# Tetris.net
KiCad netlist of a schematic drawn in EAGLE
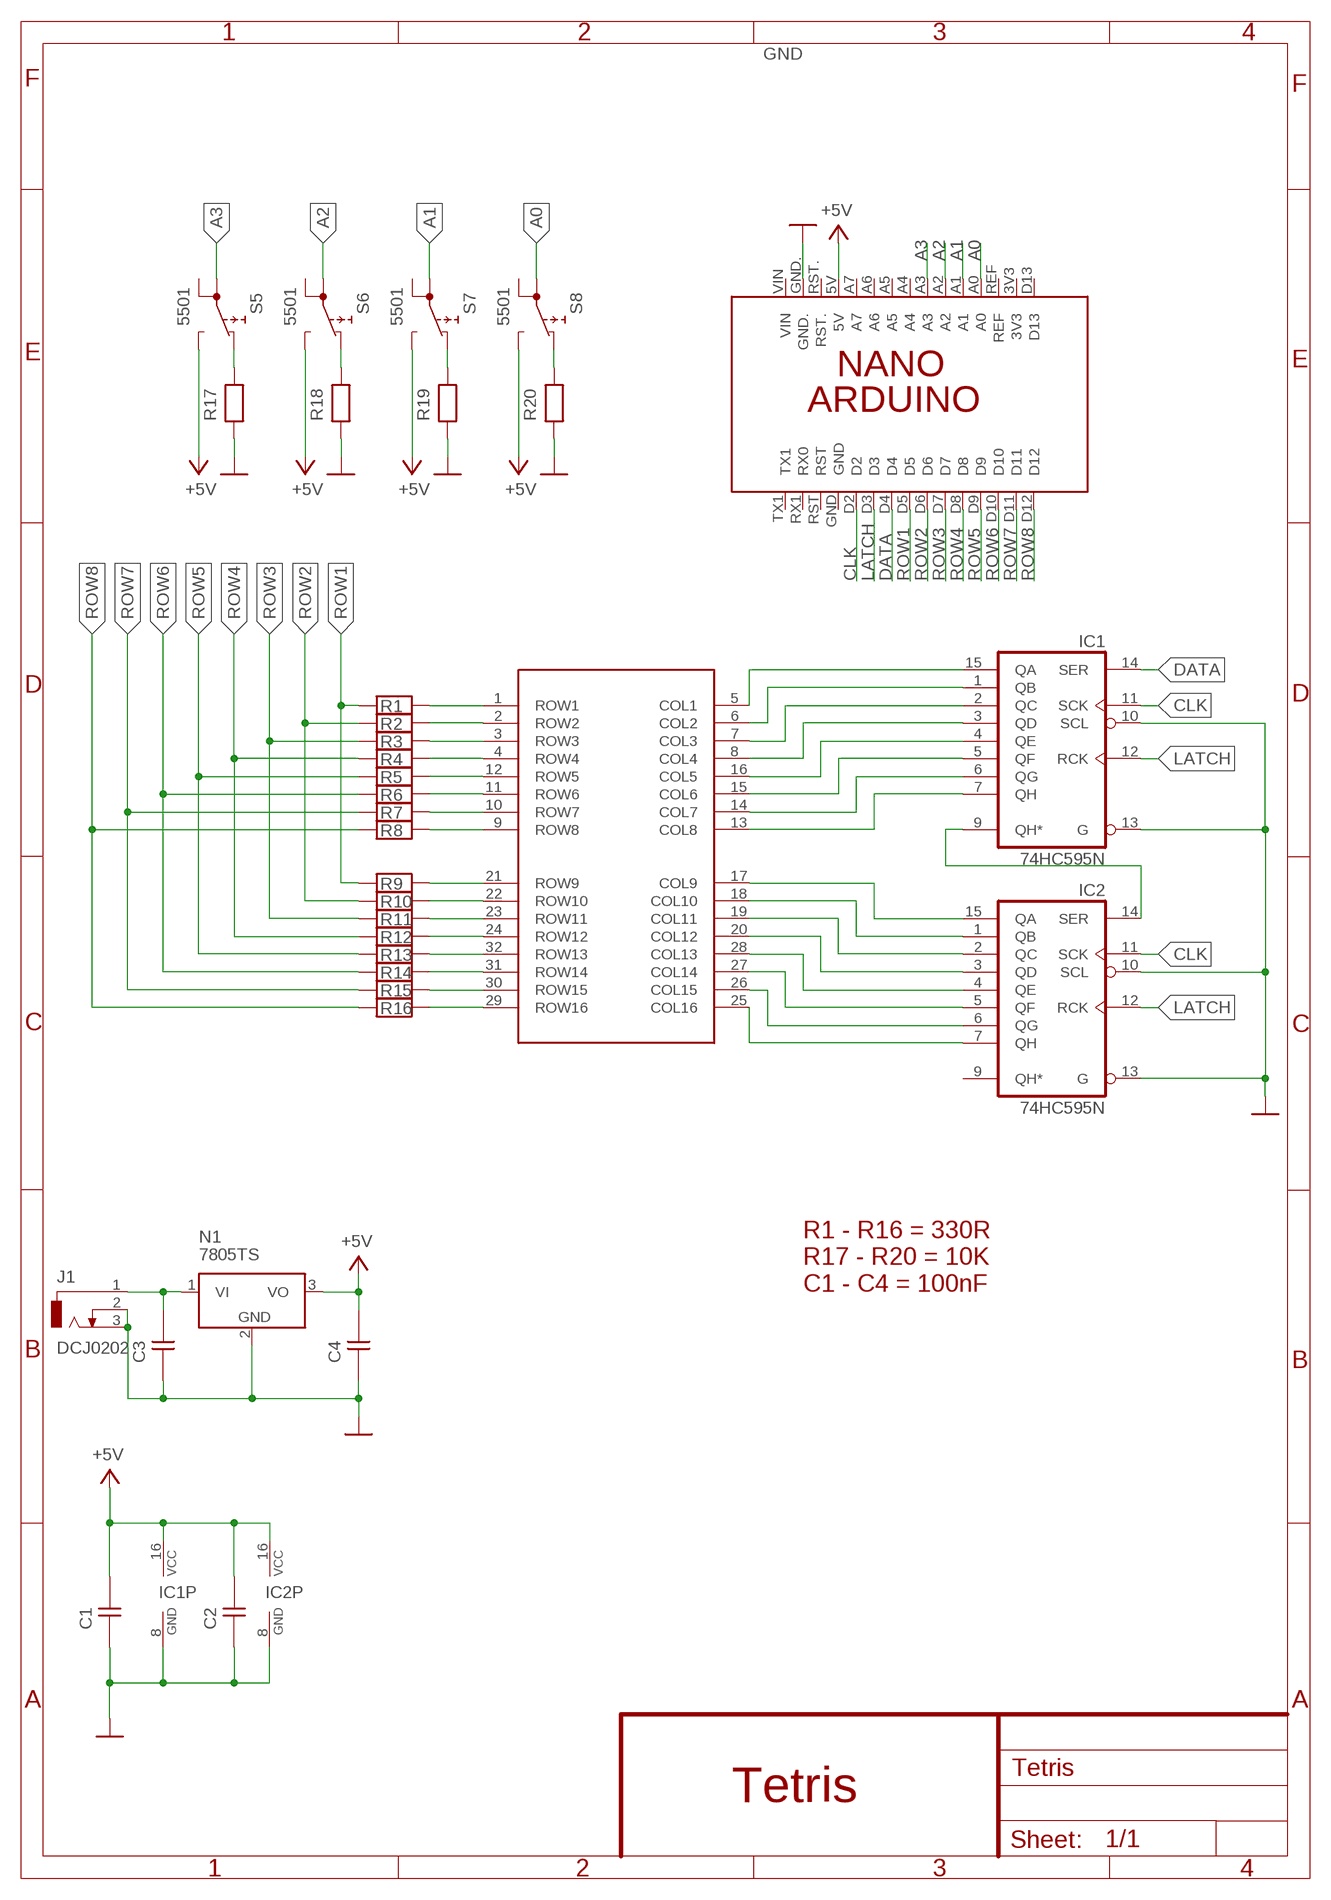
[diagram p0: schematic, sheet 1]

(export (version "E")
  (design (tool "Eeschema 10.0.6"))
  (components
    (comp (ref "C1")
      (value "C-7.5")
      (footprint "eagle-import:C-7,5")
      (libsource (lib "eagle-import") (part "C-7.5"))
    )
    (comp (ref "C2")
      (value "C-7.5")
      (footprint "eagle-import:C-7,5")
      (libsource (lib "eagle-import") (part "C-7.5"))
    )
    (comp (ref "C3")
      (value "C-7.5")
      (footprint "eagle-import:C-7,5")
      (libsource (lib "eagle-import") (part "C-7.5"))
    )
    (comp (ref "C4")
      (value "C-7.5")
      (footprint "eagle-import:C-7,5")
      (libsource (lib "eagle-import") (part "C-7.5"))
    )
    (comp (ref "IC1")
      (value "74HC595N")
      (footprint "eagle-import:DIL16")
      (libsource (lib "eagle-import") (part "74595NHC"))
    )
    (comp (ref "IC2")
      (value "74HC595N")
      (footprint "eagle-import:DIL16")
      (libsource (lib "eagle-import") (part "74595NHC"))
    )
    (comp (ref "J1")
      (value "DCJ0202")
      (footprint "eagle-import:DCJ0202")
      (libsource (lib "eagle-import") (part "DCJ0202"))
    )
    (comp (ref "N1")
      (value "7805TS")
      (footprint "eagle-import:TO-220S")
      (libsource (lib "eagle-import") (part "7805TS"))
    )
    (comp (ref "PCB1")
      (value "ARDUINO_NANO")
      (footprint "eagle-import:ARDUINO_NANO")
      (libsource (lib "eagle-import") (part "ARDUINO_NANO"))
    )
    (comp (ref "R1")
      (value "R-10")
      (footprint "eagle-import:R-10")
      (libsource (lib "eagle-import") (part "R-10"))
    )
    (comp (ref "R2")
      (value "R-10")
      (footprint "eagle-import:R-10")
      (libsource (lib "eagle-import") (part "R-10"))
    )
    (comp (ref "R3")
      (value "R-10")
      (footprint "eagle-import:R-10")
      (libsource (lib "eagle-import") (part "R-10"))
    )
    (comp (ref "R4")
      (value "R-10")
      (footprint "eagle-import:R-10")
      (libsource (lib "eagle-import") (part "R-10"))
    )
    (comp (ref "R5")
      (value "R-10")
      (footprint "eagle-import:R-10")
      (libsource (lib "eagle-import") (part "R-10"))
    )
    (comp (ref "R6")
      (value "R-10")
      (footprint "eagle-import:R-10")
      (libsource (lib "eagle-import") (part "R-10"))
    )
    (comp (ref "R7")
      (value "R-10")
      (footprint "eagle-import:R-10")
      (libsource (lib "eagle-import") (part "R-10"))
    )
    (comp (ref "R8")
      (value "R-10")
      (footprint "eagle-import:R-10")
      (libsource (lib "eagle-import") (part "R-10"))
    )
    (comp (ref "R9")
      (value "R-10")
      (footprint "eagle-import:R-10")
      (libsource (lib "eagle-import") (part "R-10"))
    )
    (comp (ref "R10")
      (value "R-10")
      (footprint "eagle-import:R-10")
      (libsource (lib "eagle-import") (part "R-10"))
    )
    (comp (ref "R11")
      (value "R-10")
      (footprint "eagle-import:R-10")
      (libsource (lib "eagle-import") (part "R-10"))
    )
    (comp (ref "R12")
      (value "R-10")
      (footprint "eagle-import:R-10")
      (libsource (lib "eagle-import") (part "R-10"))
    )
    (comp (ref "R13")
      (value "R-10")
      (footprint "eagle-import:R-10")
      (libsource (lib "eagle-import") (part "R-10"))
    )
    (comp (ref "R14")
      (value "R-10")
      (footprint "eagle-import:R-10")
      (libsource (lib "eagle-import") (part "R-10"))
    )
    (comp (ref "R15")
      (value "R-10")
      (footprint "eagle-import:R-10")
      (libsource (lib "eagle-import") (part "R-10"))
    )
    (comp (ref "R16")
      (value "R-10")
      (footprint "eagle-import:R-10")
      (libsource (lib "eagle-import") (part "R-10"))
    )
    (comp (ref "R17")
      (value "R-10")
      (footprint "eagle-import:R-10")
      (libsource (lib "eagle-import") (part "R-10"))
    )
    (comp (ref "R18")
      (value "R-10")
      (footprint "eagle-import:R-10")
      (libsource (lib "eagle-import") (part "R-10"))
    )
    (comp (ref "R19")
      (value "R-10")
      (footprint "eagle-import:R-10")
      (libsource (lib "eagle-import") (part "R-10"))
    )
    (comp (ref "R20")
      (value "R-10")
      (footprint "eagle-import:R-10")
      (libsource (lib "eagle-import") (part "R-10"))
    )
    (comp (ref "S5")
      (value "5501")
      (footprint "eagle-import:5501")
      (libsource (lib "eagle-import") (part "55?01"))
    )
    (comp (ref "S6")
      (value "5501")
      (footprint "eagle-import:5501")
      (libsource (lib "eagle-import") (part "55?01"))
    )
    (comp (ref "S7")
      (value "5501")
      (footprint "eagle-import:5501")
      (libsource (lib "eagle-import") (part "55?01"))
    )
    (comp (ref "S8")
      (value "5501")
      (footprint "eagle-import:5501")
      (libsource (lib "eagle-import") (part "55?01"))
    )
    (comp (ref "U$9")
      (value "DOT_MATRIX")
      (footprint "eagle-import:SH")
      (libsource (lib "eagle-import") (part "DOT_MATRIX"))
    )
  )
  (nets
    (net (code "1") (name "+5V") (class "Default")
      (node (ref "C1") (pin "2") (pinfunction "2_2") (pintype "passive"))
      (node (ref "C2") (pin "2") (pinfunction "2_2") (pintype "passive"))
      (node (ref "C4") (pin "2") (pinfunction "2_2") (pintype "passive"))
      (node (ref "IC1") (pin "16") (pinfunction "VCC_16") (pintype "power_in"))
      (node (ref "IC2") (pin "16") (pinfunction "VCC_16") (pintype "power_in"))
      (node (ref "N1") (pin "3") (pinfunction "VO_3") (pintype "output"))
      (node (ref "PCB1") (pin "5V") (pinfunction "5V_5V") (pintype "bidirectional"))
      (node (ref "S5") (pin "NC") (pinfunction "NO_NC") (pintype "passive"))
      (node (ref "S6") (pin "NC") (pinfunction "NO_NC") (pintype "passive"))
      (node (ref "S7") (pin "NC") (pinfunction "NO_NC") (pintype "passive"))
      (node (ref "S8") (pin "NC") (pinfunction "NO_NC") (pintype "passive"))
    )
    (net (code "2") (name "A0") (class "Default")
      (node (ref "PCB1") (pin "A0") (pinfunction "A0_A0") (pintype "bidirectional"))
      (node (ref "S8") (pin "1A") (pinfunction "1A_1A") (pintype "passive"))
    )
    (net (code "3") (name "A1") (class "Default")
      (node (ref "PCB1") (pin "A1") (pinfunction "A1_A1") (pintype "bidirectional"))
      (node (ref "S7") (pin "1A") (pinfunction "1A_1A") (pintype "passive"))
    )
    (net (code "4") (name "A2") (class "Default")
      (node (ref "PCB1") (pin "A2") (pinfunction "A2_A2") (pintype "bidirectional"))
      (node (ref "S6") (pin "1A") (pinfunction "1A_1A") (pintype "passive"))
    )
    (net (code "5") (name "A3") (class "Default")
      (node (ref "PCB1") (pin "A3") (pinfunction "A3_A3") (pintype "bidirectional"))
      (node (ref "S5") (pin "1A") (pinfunction "1A_1A") (pintype "passive"))
    )
    (net (code "6") (name "CLK") (class "Default")
      (node (ref "IC1") (pin "11") (pinfunction "SCK_11") (pintype "input"))
      (node (ref "IC2") (pin "11") (pinfunction "SCK_11") (pintype "input"))
      (node (ref "PCB1") (pin "D2") (pinfunction "D2_D2") (pintype "bidirectional"))
    )
    (net (code "7") (name "DATA") (class "Default")
      (node (ref "IC1") (pin "14") (pinfunction "SER_14") (pintype "input"))
      (node (ref "PCB1") (pin "D4") (pinfunction "D4_D4") (pintype "bidirectional"))
    )
    (net (code "8") (name "GND") (class "Default")
      (node (ref "C1") (pin "1") (pinfunction "1_1") (pintype "passive"))
      (node (ref "C2") (pin "1") (pinfunction "1_1") (pintype "passive"))
      (node (ref "C3") (pin "1") (pinfunction "1_1") (pintype "passive"))
      (node (ref "C4") (pin "1") (pinfunction "1_1") (pintype "passive"))
      (node (ref "IC1") (pin "10") (pinfunction "SCL_10") (pintype "input"))
      (node (ref "IC1") (pin "13") (pinfunction "G_13") (pintype "input"))
      (node (ref "IC1") (pin "8") (pinfunction "GND_8") (pintype "power_in"))
      (node (ref "IC2") (pin "10") (pinfunction "SCL_10") (pintype "input"))
      (node (ref "IC2") (pin "13") (pinfunction "G_13") (pintype "input"))
      (node (ref "IC2") (pin "8") (pinfunction "GND_8") (pintype "power_in"))
      (node (ref "J1") (pin "2") (pinfunction "2_2") (pintype "passive"))
      (node (ref "J1") (pin "3") (pinfunction "3_3") (pintype "passive"))
      (node (ref "N1") (pin "2") (pinfunction "GND_2") (pintype "input"))
      (node (ref "PCB1") (pin "GND.") (pinfunction "GND._GND.") (pintype "bidirectional"))
      (node (ref "R17") (pin "1") (pinfunction "1_1") (pintype "passive"))
      (node (ref "R18") (pin "1") (pinfunction "1_1") (pintype "passive"))
      (node (ref "R19") (pin "1") (pinfunction "1_1") (pintype "passive"))
      (node (ref "R20") (pin "1") (pinfunction "1_1") (pintype "passive"))
    )
    (net (code "9") (name "LATCH") (class "Default")
      (node (ref "IC1") (pin "12") (pinfunction "RCK_12") (pintype "input"))
      (node (ref "IC2") (pin "12") (pinfunction "RCK_12") (pintype "input"))
      (node (ref "PCB1") (pin "D3") (pinfunction "D3_D3") (pintype "bidirectional"))
    )
    (net (code "10") (name "Net-(IC1A-QA)") (class "Default")
      (node (ref "IC1") (pin "15") (pinfunction "QA_15") (pintype "tri_state"))
      (node (ref "U$9") (pin "5") (pinfunction "COL1_5") (pintype "bidirectional"))
    )
    (net (code "11") (name "Net-(IC1A-QB)") (class "Default")
      (node (ref "IC1") (pin "1") (pinfunction "QB_1") (pintype "tri_state"))
      (node (ref "U$9") (pin "6") (pinfunction "COL2_6") (pintype "bidirectional"))
    )
    (net (code "12") (name "Net-(IC1A-QC)") (class "Default")
      (node (ref "IC1") (pin "2") (pinfunction "QC_2") (pintype "tri_state"))
      (node (ref "U$9") (pin "7") (pinfunction "COL3_7") (pintype "bidirectional"))
    )
    (net (code "13") (name "Net-(IC1A-QD)") (class "Default")
      (node (ref "IC1") (pin "3") (pinfunction "QD_3") (pintype "tri_state"))
      (node (ref "U$9") (pin "8") (pinfunction "COL4_8") (pintype "bidirectional"))
    )
    (net (code "14") (name "Net-(IC1A-QE)") (class "Default")
      (node (ref "IC1") (pin "4") (pinfunction "QE_4") (pintype "tri_state"))
      (node (ref "U$9") (pin "16") (pinfunction "COL5_16") (pintype "bidirectional"))
    )
    (net (code "15") (name "Net-(IC1A-QF)") (class "Default")
      (node (ref "IC1") (pin "5") (pinfunction "QF_5") (pintype "tri_state"))
      (node (ref "U$9") (pin "15") (pinfunction "COL6_15") (pintype "bidirectional"))
    )
    (net (code "16") (name "Net-(IC1A-QG)") (class "Default")
      (node (ref "IC1") (pin "6") (pinfunction "QG_6") (pintype "tri_state"))
      (node (ref "U$9") (pin "14") (pinfunction "COL7_14") (pintype "bidirectional"))
    )
    (net (code "17") (name "Net-(IC1A-QH)") (class "Default")
      (node (ref "IC1") (pin "7") (pinfunction "QH_7") (pintype "tri_state"))
      (node (ref "U$9") (pin "13") (pinfunction "COL8_13") (pintype "bidirectional"))
    )
    (net (code "18") (name "Net-(IC1A-QH*)") (class "Default")
      (node (ref "IC1") (pin "9") (pinfunction "QH*_9") (pintype "tri_state"))
      (node (ref "IC2") (pin "14") (pinfunction "SER_14") (pintype "input"))
    )
    (net (code "19") (name "Net-(IC2A-QA)") (class "Default")
      (node (ref "IC2") (pin "15") (pinfunction "QA_15") (pintype "tri_state"))
      (node (ref "U$9") (pin "17") (pinfunction "COL9_17") (pintype "bidirectional"))
    )
    (net (code "20") (name "Net-(IC2A-QB)") (class "Default")
      (node (ref "IC2") (pin "1") (pinfunction "QB_1") (pintype "tri_state"))
      (node (ref "U$9") (pin "18") (pinfunction "COL10_18") (pintype "bidirectional"))
    )
    (net (code "21") (name "Net-(IC2A-QC)") (class "Default")
      (node (ref "IC2") (pin "2") (pinfunction "QC_2") (pintype "tri_state"))
      (node (ref "U$9") (pin "19") (pinfunction "COL11_19") (pintype "bidirectional"))
    )
    (net (code "22") (name "Net-(IC2A-QD)") (class "Default")
      (node (ref "IC2") (pin "3") (pinfunction "QD_3") (pintype "tri_state"))
      (node (ref "U$9") (pin "20") (pinfunction "COL12_20") (pintype "bidirectional"))
    )
    (net (code "23") (name "Net-(IC2A-QE)") (class "Default")
      (node (ref "IC2") (pin "4") (pinfunction "QE_4") (pintype "tri_state"))
      (node (ref "U$9") (pin "28") (pinfunction "COL13_28") (pintype "bidirectional"))
    )
    (net (code "24") (name "Net-(IC2A-QF)") (class "Default")
      (node (ref "IC2") (pin "5") (pinfunction "QF_5") (pintype "tri_state"))
      (node (ref "U$9") (pin "27") (pinfunction "COL14_27") (pintype "bidirectional"))
    )
    (net (code "25") (name "Net-(IC2A-QG)") (class "Default")
      (node (ref "IC2") (pin "6") (pinfunction "QG_6") (pintype "tri_state"))
      (node (ref "U$9") (pin "26") (pinfunction "COL15_26") (pintype "bidirectional"))
    )
    (net (code "26") (name "Net-(IC2A-QH)") (class "Default")
      (node (ref "IC2") (pin "7") (pinfunction "QH_7") (pintype "tri_state"))
      (node (ref "U$9") (pin "25") (pinfunction "COL16_25") (pintype "bidirectional"))
    )
    (net (code "27") (name "Net-(N1-VI)") (class "Default")
      (node (ref "C3") (pin "2") (pinfunction "2_2") (pintype "passive"))
      (node (ref "J1") (pin "1") (pinfunction "1_1") (pintype "passive"))
      (node (ref "N1") (pin "1") (pinfunction "VI_1") (pintype "input"))
    )
    (net (code "28") (name "Net-(S5-NC)") (class "Default")
      (node (ref "R17") (pin "2") (pinfunction "2_2") (pintype "passive"))
      (node (ref "S5") (pin "NO") (pinfunction "NC_NO") (pintype "passive"))
    )
    (net (code "29") (name "Net-(S6-NC)") (class "Default")
      (node (ref "R18") (pin "2") (pinfunction "2_2") (pintype "passive"))
      (node (ref "S6") (pin "NO") (pinfunction "NC_NO") (pintype "passive"))
    )
    (net (code "30") (name "Net-(S7-NC)") (class "Default")
      (node (ref "R19") (pin "2") (pinfunction "2_2") (pintype "passive"))
      (node (ref "S7") (pin "NO") (pinfunction "NC_NO") (pintype "passive"))
    )
    (net (code "31") (name "Net-(S8-NC)") (class "Default")
      (node (ref "R20") (pin "2") (pinfunction "2_2") (pintype "passive"))
      (node (ref "S8") (pin "NO") (pinfunction "NC_NO") (pintype "passive"))
    )
    (net (code "32") (name "Net-(U$9-ROW1)") (class "Default")
      (node (ref "R1") (pin "2") (pinfunction "2_2") (pintype "passive"))
      (node (ref "U$9") (pin "1") (pinfunction "ROW1_1") (pintype "bidirectional"))
    )
    (net (code "33") (name "Net-(U$9-ROW2)") (class "Default")
      (node (ref "R2") (pin "2") (pinfunction "2_2") (pintype "passive"))
      (node (ref "U$9") (pin "2") (pinfunction "ROW2_2") (pintype "bidirectional"))
    )
    (net (code "34") (name "Net-(U$9-ROW3)") (class "Default")
      (node (ref "R3") (pin "2") (pinfunction "2_2") (pintype "passive"))
      (node (ref "U$9") (pin "3") (pinfunction "ROW3_3") (pintype "bidirectional"))
    )
    (net (code "35") (name "Net-(U$9-ROW4)") (class "Default")
      (node (ref "R4") (pin "2") (pinfunction "2_2") (pintype "passive"))
      (node (ref "U$9") (pin "4") (pinfunction "ROW4_4") (pintype "bidirectional"))
    )
    (net (code "36") (name "Net-(U$9-ROW5)") (class "Default")
      (node (ref "R5") (pin "2") (pinfunction "2_2") (pintype "passive"))
      (node (ref "U$9") (pin "12") (pinfunction "ROW5_12") (pintype "bidirectional"))
    )
    (net (code "37") (name "Net-(U$9-ROW6)") (class "Default")
      (node (ref "R6") (pin "2") (pinfunction "2_2") (pintype "passive"))
      (node (ref "U$9") (pin "11") (pinfunction "ROW6_11") (pintype "bidirectional"))
    )
    (net (code "38") (name "Net-(U$9-ROW7)") (class "Default")
      (node (ref "R7") (pin "2") (pinfunction "2_2") (pintype "passive"))
      (node (ref "U$9") (pin "10") (pinfunction "ROW7_10") (pintype "bidirectional"))
    )
    (net (code "39") (name "Net-(U$9-ROW8)") (class "Default")
      (node (ref "R8") (pin "2") (pinfunction "2_2") (pintype "passive"))
      (node (ref "U$9") (pin "9") (pinfunction "ROW8_9") (pintype "bidirectional"))
    )
    (net (code "40") (name "Net-(U$9-ROW9)") (class "Default")
      (node (ref "R9") (pin "2") (pinfunction "2_2") (pintype "passive"))
      (node (ref "U$9") (pin "21") (pinfunction "ROW9_21") (pintype "bidirectional"))
    )
    (net (code "41") (name "Net-(U$9-ROW10)") (class "Default")
      (node (ref "R10") (pin "2") (pinfunction "2_2") (pintype "passive"))
      (node (ref "U$9") (pin "22") (pinfunction "ROW10_22") (pintype "bidirectional"))
    )
    (net (code "42") (name "Net-(U$9-ROW11)") (class "Default")
      (node (ref "R11") (pin "2") (pinfunction "2_2") (pintype "passive"))
      (node (ref "U$9") (pin "23") (pinfunction "ROW11_23") (pintype "bidirectional"))
    )
    (net (code "43") (name "Net-(U$9-ROW12)") (class "Default")
      (node (ref "R12") (pin "2") (pinfunction "2_2") (pintype "passive"))
      (node (ref "U$9") (pin "24") (pinfunction "ROW12_24") (pintype "bidirectional"))
    )
    (net (code "44") (name "Net-(U$9-ROW13)") (class "Default")
      (node (ref "R13") (pin "2") (pinfunction "2_2") (pintype "passive"))
      (node (ref "U$9") (pin "32") (pinfunction "ROW13_32") (pintype "bidirectional"))
    )
    (net (code "45") (name "Net-(U$9-ROW14)") (class "Default")
      (node (ref "R14") (pin "2") (pinfunction "2_2") (pintype "passive"))
      (node (ref "U$9") (pin "31") (pinfunction "ROW14_31") (pintype "bidirectional"))
    )
    (net (code "46") (name "Net-(U$9-ROW15)") (class "Default")
      (node (ref "R15") (pin "2") (pinfunction "2_2") (pintype "passive"))
      (node (ref "U$9") (pin "30") (pinfunction "ROW15_30") (pintype "bidirectional"))
    )
    (net (code "47") (name "Net-(U$9-ROW16)") (class "Default")
      (node (ref "R16") (pin "2") (pinfunction "2_2") (pintype "passive"))
      (node (ref "U$9") (pin "29") (pinfunction "ROW16_29") (pintype "bidirectional"))
    )
    (net (code "48") (name "ROW1") (class "Default")
      (node (ref "PCB1") (pin "D5") (pinfunction "D5_D5") (pintype "bidirectional"))
      (node (ref "R1") (pin "1") (pinfunction "1_1") (pintype "passive"))
      (node (ref "R9") (pin "1") (pinfunction "1_1") (pintype "passive"))
    )
    (net (code "49") (name "ROW2") (class "Default")
      (node (ref "PCB1") (pin "D6") (pinfunction "D6_D6") (pintype "bidirectional"))
      (node (ref "R10") (pin "1") (pinfunction "1_1") (pintype "passive"))
      (node (ref "R2") (pin "1") (pinfunction "1_1") (pintype "passive"))
    )
    (net (code "50") (name "ROW3") (class "Default")
      (node (ref "PCB1") (pin "D7") (pinfunction "D7_D7") (pintype "bidirectional"))
      (node (ref "R11") (pin "1") (pinfunction "1_1") (pintype "passive"))
      (node (ref "R3") (pin "1") (pinfunction "1_1") (pintype "passive"))
    )
    (net (code "51") (name "ROW4") (class "Default")
      (node (ref "PCB1") (pin "D8") (pinfunction "D8_D8") (pintype "bidirectional"))
      (node (ref "R12") (pin "1") (pinfunction "1_1") (pintype "passive"))
      (node (ref "R4") (pin "1") (pinfunction "1_1") (pintype "passive"))
    )
    (net (code "52") (name "ROW5") (class "Default")
      (node (ref "PCB1") (pin "D9") (pinfunction "D9_D9") (pintype "bidirectional"))
      (node (ref "R13") (pin "1") (pinfunction "1_1") (pintype "passive"))
      (node (ref "R5") (pin "1") (pinfunction "1_1") (pintype "passive"))
    )
    (net (code "53") (name "ROW6") (class "Default")
      (node (ref "PCB1") (pin "D10") (pinfunction "D10_D10") (pintype "bidirectional"))
      (node (ref "R14") (pin "1") (pinfunction "1_1") (pintype "passive"))
      (node (ref "R6") (pin "1") (pinfunction "1_1") (pintype "passive"))
    )
    (net (code "54") (name "ROW7") (class "Default")
      (node (ref "PCB1") (pin "D11") (pinfunction "D11_D11") (pintype "bidirectional"))
      (node (ref "R15") (pin "1") (pinfunction "1_1") (pintype "passive"))
      (node (ref "R7") (pin "1") (pinfunction "1_1") (pintype "passive"))
    )
    (net (code "55") (name "ROW8") (class "Default")
      (node (ref "PCB1") (pin "D12") (pinfunction "D12_D12") (pintype "bidirectional"))
      (node (ref "R16") (pin "1") (pinfunction "1_1") (pintype "passive"))
      (node (ref "R8") (pin "1") (pinfunction "1_1") (pintype "passive"))
    )
    (net (code "56") (name "unconnected-(IC2A-QH*-Pad9)") (class "Default")
      (node (ref "IC2") (pin "9") (pinfunction "QH*_9") (pintype "tri_state"))
    )
    (net (code "57") (name "unconnected-(PCB1-Pad3V3)") (class "Default")
      (node (ref "PCB1") (pin "3V3") (pinfunction "3V3_3V3") (pintype "bidirectional"))
    )
    (net (code "58") (name "unconnected-(PCB1-PadA4)") (class "Default")
      (node (ref "PCB1") (pin "A4") (pinfunction "A4_A4") (pintype "bidirectional"))
    )
    (net (code "59") (name "unconnected-(PCB1-PadA5)") (class "Default")
      (node (ref "PCB1") (pin "A5") (pinfunction "A5_A5") (pintype "bidirectional"))
    )
    (net (code "60") (name "unconnected-(PCB1-PadA6)") (class "Default")
      (node (ref "PCB1") (pin "A6") (pinfunction "A6_A6") (pintype "bidirectional"))
    )
    (net (code "61") (name "unconnected-(PCB1-PadA7)") (class "Default")
      (node (ref "PCB1") (pin "A7") (pinfunction "A7_A7") (pintype "bidirectional"))
    )
    (net (code "62") (name "unconnected-(PCB1-PadD13)") (class "Default")
      (node (ref "PCB1") (pin "D13") (pinfunction "D13_D13") (pintype "bidirectional"))
    )
    (net (code "63") (name "unconnected-(PCB1-PadGND)") (class "Default")
      (node (ref "PCB1") (pin "GND") (pinfunction "GND_GND") (pintype "bidirectional"))
    )
    (net (code "64") (name "unconnected-(PCB1-PadREF)") (class "Default")
      (node (ref "PCB1") (pin "REF") (pinfunction "REF_REF") (pintype "bidirectional"))
    )
    (net (code "65") (name "unconnected-(PCB1-PadRST)") (class "Default")
      (node (ref "PCB1") (pin "RST") (pinfunction "RST_RST") (pintype "bidirectional"))
    )
    (net (code "66") (name "unconnected-(PCB1-PadRST.)") (class "Default")
      (node (ref "PCB1") (pin "RST.") (pinfunction "RST._RST.") (pintype "bidirectional"))
    )
    (net (code "67") (name "unconnected-(PCB1-PadTX1)") (class "Default")
      (node (ref "PCB1") (pin "TX1") (pinfunction "TX1_TX1") (pintype "bidirectional"))
    )
    (net (code "68") (name "unconnected-(PCB1-PadVIN)") (class "Default")
      (node (ref "PCB1") (pin "VIN") (pinfunction "VIN_VIN") (pintype "bidirectional"))
    )
    (net (code "69") (name "unconnected-(PCB1-RX0-PadRX1)") (class "Default")
      (node (ref "PCB1") (pin "RX1") (pinfunction "RX0_RX1") (pintype "bidirectional"))
    )
    (net (code "70") (name "unconnected-(S5-Pad1B)") (class "Default")
      (node (ref "S5") (pin "1B") (pinfunction "1B_1B") (pintype "passive"))
    )
    (net (code "71") (name "unconnected-(S6-Pad1B)") (class "Default")
      (node (ref "S6") (pin "1B") (pinfunction "1B_1B") (pintype "passive"))
    )
    (net (code "72") (name "unconnected-(S7-Pad1B)") (class "Default")
      (node (ref "S7") (pin "1B") (pinfunction "1B_1B") (pintype "passive"))
    )
    (net (code "73") (name "unconnected-(S8-Pad1B)") (class "Default")
      (node (ref "S8") (pin "1B") (pinfunction "1B_1B") (pintype "passive"))
    )
  )
)
